# 2relay.net
KiCad netlist of a schematic drawn in EAGLE
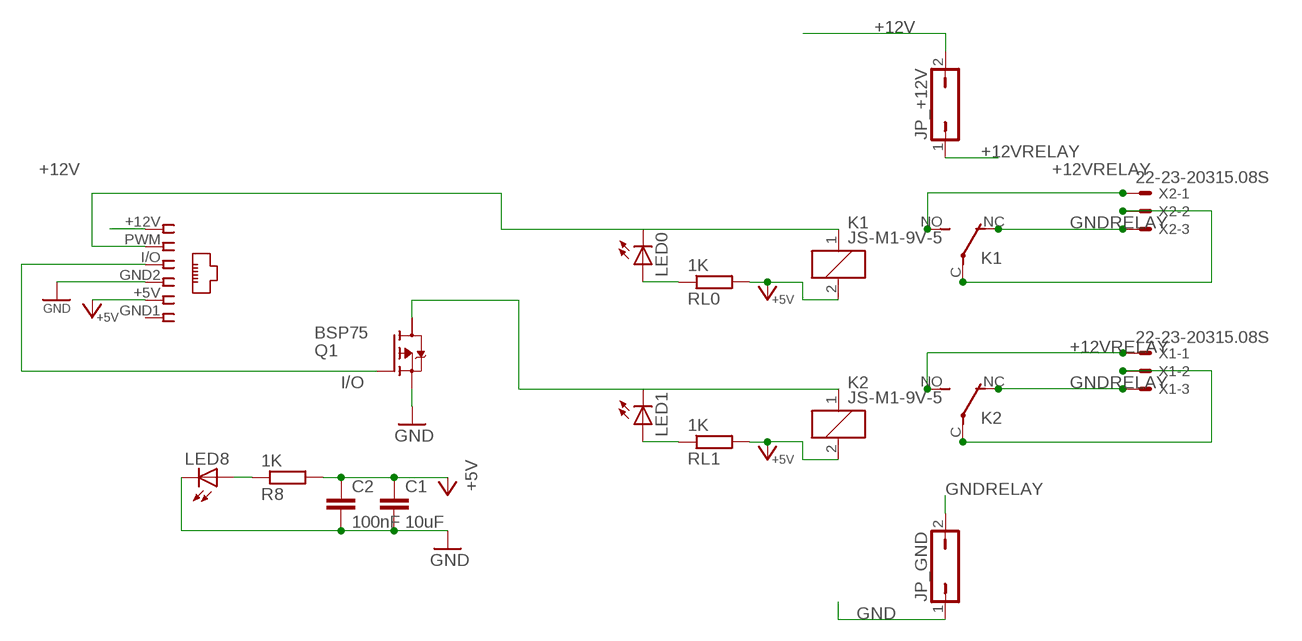
[diagram p0: schematic, sheet 1]

(export (version "E")
  (design (tool "Eeschema 10.0.6"))
  (components
    (comp (ref "C1")
      (value "10uF")
      (footprint "eagle-import:C1206")
      (libsource (lib "eagle-import") (part "C-EUC1206"))
    )
    (comp (ref "C2")
      (value "100nF")
      (footprint "eagle-import:C1206")
      (libsource (lib "eagle-import") (part "C-EUC1206"))
    )
    (comp (ref "I/O_PWM")
      (value "I2C 1")
      (footprint "eagle-import:RJ12-STRAIGHT")
      (libsource (lib "eagle-import") (part "RJ12STRAIGHT"))
    )
    (comp (ref "JP_+12V")
      (value "JP1Q")
      (footprint "eagle-import:JP1")
      (libsource (lib "eagle-import") (part "JP1Q"))
    )
    (comp (ref "JP_GND")
      (value "JP1Q")
      (footprint "eagle-import:JP1")
      (libsource (lib "eagle-import") (part "JP1Q"))
    )
    (comp (ref "K1")
      (value "JS-M1-9V-5")
      (footprint "eagle-import:JS-M")
      (libsource (lib "eagle-import") (part "JS-M1-9V-5"))
    )
    (comp (ref "K2")
      (value "JS-M1-9V-5")
      (footprint "eagle-import:JS-M")
      (libsource (lib "eagle-import") (part "JS-M1-9V-5"))
    )
    (comp (ref "LED0")
      (value "LED1206")
      (footprint "eagle-import:LED-1206")
      (libsource (lib "eagle-import") (part "LED1206"))
    )
    (comp (ref "LED1")
      (value "LED1206")
      (footprint "eagle-import:LED-1206")
      (libsource (lib "eagle-import") (part "LED1206"))
    )
    (comp (ref "LED8")
      (value "LED1206")
      (footprint "eagle-import:LED-1206")
      (libsource (lib "eagle-import") (part "LED1206"))
    )
    (comp (ref "Q1")
      (value "BSP75")
      (footprint "eagle-import:PG-SOT-223")
      (libsource (lib "eagle-import") (part "BSP613P"))
    )
    (comp (ref "R8")
      (value "1K")
      (footprint "eagle-import:M1206")
      (libsource (lib "eagle-import") (part "R-EU_M1206"))
    )
    (comp (ref "RL0")
      (value "1K")
      (footprint "eagle-import:M1206")
      (libsource (lib "eagle-import") (part "R-EU_M1206"))
    )
    (comp (ref "RL1")
      (value "1K")
      (footprint "eagle-import:M1206")
      (libsource (lib "eagle-import") (part "R-EU_M1206"))
    )
    (comp (ref "X1")
      (value "22-23-20315.08S")
      (footprint "eagle-import:3-PIN-5.08S")
      (libsource (lib "eagle-import") (part "22-23-20315.08S"))
    )
    (comp (ref "X2")
      (value "22-23-20315.08S")
      (footprint "eagle-import:3-PIN-5.08S")
      (libsource (lib "eagle-import") (part "22-23-20315.08S"))
    )
  )
  (nets
    (net (code "1") (name "+5V") (class "Default")
      (node (ref "C1") (pin "1") (pinfunction "1_1") (pintype "passive"))
      (node (ref "C2") (pin "1") (pinfunction "1_1") (pintype "passive"))
      (node (ref "I/O_PWM") (pin "+5V") (pinfunction "5_+5V") (pintype "bidirectional"))
      (node (ref "K1") (pin "2") (pinfunction "2_2") (pintype "passive"))
      (node (ref "K2") (pin "2") (pinfunction "2_2") (pintype "passive"))
      (node (ref "R8") (pin "2") (pinfunction "2_2") (pintype "passive"))
      (node (ref "RL0") (pin "2") (pinfunction "2_2") (pintype "passive"))
      (node (ref "RL1") (pin "2") (pinfunction "2_2") (pintype "passive"))
    )
    (net (code "2") (name "/+12V") (class "Default")
      (node (ref "I/O_PWM") (pin "+12V") (pinfunction "1_+12V") (pintype "bidirectional"))
      (node (ref "JP_+12V") (pin "2") (pinfunction "2_2") (pintype "passive"))
    )
    (net (code "3") (name "/+12VRELAY") (class "Default")
      (node (ref "JP_+12V") (pin "1") (pinfunction "1_1") (pintype "passive"))
      (node (ref "K1") (pin "NO") (pinfunction "S_NO") (pintype "passive"))
      (node (ref "K2") (pin "NO") (pinfunction "S_NO") (pintype "passive"))
      (node (ref "X1") (pin "1") (pinfunction "S_1") (pintype "passive"))
      (node (ref "X2") (pin "1") (pinfunction "S_1") (pintype "passive"))
    )
    (net (code "4") (name "/GNDRELAY") (class "Default")
      (node (ref "JP_GND") (pin "2") (pinfunction "2_2") (pintype "passive"))
      (node (ref "K1") (pin "NC") (pinfunction "O_NC") (pintype "passive"))
      (node (ref "K2") (pin "NC") (pinfunction "O_NC") (pintype "passive"))
      (node (ref "X1") (pin "3") (pinfunction "S_3") (pintype "passive"))
      (node (ref "X2") (pin "3") (pinfunction "S_3") (pintype "passive"))
    )
    (net (code "5") (name "/I{slash}O") (class "Default")
      (node (ref "I/O_PWM") (pin "I/O") (pinfunction "3_I/O") (pintype "bidirectional"))
      (node (ref "Q1") (pin "1") (pinfunction "G_1") (pintype "passive"))
    )
    (net (code "6") (name "GND") (class "Default")
      (node (ref "C1") (pin "2") (pinfunction "2_2") (pintype "passive"))
      (node (ref "C2") (pin "2") (pinfunction "2_2") (pintype "passive"))
      (node (ref "I/O_PWM") (pin "GND2") (pinfunction "4_GND2") (pintype "bidirectional"))
      (node (ref "JP_GND") (pin "1") (pinfunction "1_1") (pintype "passive"))
      (node (ref "LED8") (pin "C") (pinfunction "C_C") (pintype "passive"))
      (node (ref "Q1") (pin "3") (pinfunction "S_3") (pintype "passive"))
    )
    (net (code "7") (name "Net-(I/O_PWM-2)") (class "Default")
      (node (ref "I/O_PWM") (pin "PWM") (pinfunction "2_PWM") (pintype "bidirectional"))
      (node (ref "K1") (pin "1") (pinfunction "1_1") (pintype "passive"))
      (node (ref "LED0") (pin "C") (pinfunction "C_C") (pintype "passive"))
    )
    (net (code "8") (name "Net-(K1B-P)") (class "Default")
      (node (ref "K1") (pin "C") (pinfunction "P_C") (pintype "passive"))
      (node (ref "X2") (pin "2") (pinfunction "S_2") (pintype "passive"))
    )
    (net (code "9") (name "Net-(K2-Pad1)") (class "Default")
      (node (ref "K2") (pin "1") (pinfunction "1_1") (pintype "passive"))
      (node (ref "LED1") (pin "C") (pinfunction "C_C") (pintype "passive"))
      (node (ref "Q1") (pin "2") (pinfunction "D_2") (pintype "passive"))
    )
    (net (code "10") (name "Net-(K2B-P)") (class "Default")
      (node (ref "K2") (pin "C") (pinfunction "P_C") (pintype "passive"))
      (node (ref "X1") (pin "2") (pinfunction "S_2") (pintype "passive"))
    )
    (net (code "11") (name "Net-(LED0-PadA)") (class "Default")
      (node (ref "LED0") (pin "A") (pinfunction "A_A") (pintype "passive"))
      (node (ref "RL0") (pin "1") (pinfunction "1_1") (pintype "passive"))
    )
    (net (code "12") (name "Net-(LED1-PadA)") (class "Default")
      (node (ref "LED1") (pin "A") (pinfunction "A_A") (pintype "passive"))
      (node (ref "RL1") (pin "1") (pinfunction "1_1") (pintype "passive"))
    )
    (net (code "13") (name "Net-(LED8-PadA)") (class "Default")
      (node (ref "LED8") (pin "A") (pinfunction "A_A") (pintype "passive"))
      (node (ref "R8") (pin "1") (pinfunction "1_1") (pintype "passive"))
    )
    (net (code "14") (name "unconnected-(I/O_PWM-6-PadGND1)") (class "Default")
      (node (ref "I/O_PWM") (pin "GND1") (pinfunction "6_GND1") (pintype "bidirectional"))
    )
    (net (code "15") (name "unconnected-(Q1-D-Pad4)") (class "Default")
      (node (ref "Q1") (pin "4") (pinfunction "D_4") (pintype "passive"))
    )
  )
)
